# M.net
KiCad netlist of a schematic drawn in Altium Designer
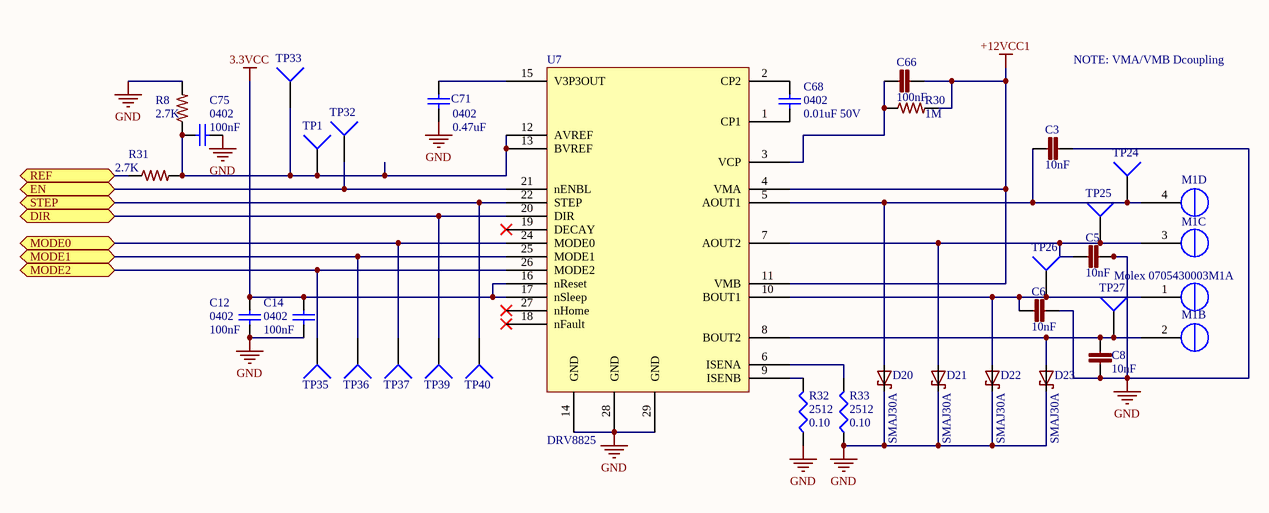
[diagram p0: M.SchDoc]

(export (version "E")
  (design (tool "Eeschema 10.0.6"))
  (components
    (comp (ref "C3")
      (value "10nF")
      (footprint "C0603")
      (description "CAP CER 0603 10nF 25V 10% X7R")
      (fields
        (field (name "MANUFACTURERPARTNUMBER") "C1608X7R1E103K080AA")
        (field (name "PUBLISHER") "UltiMachine")
      )
      (libsource (lib "3Delight") (part "C1608X7R1E103K080AA"))
    )
    (comp (ref "C5")
      (value "10nF")
      (footprint "C0603")
      (description "CAP CER 0603 10nF 25V 10% X7R")
      (fields
        (field (name "MANUFACTURERPARTNUMBER") "C1608X7R1E103K080AA")
        (field (name "PUBLISHER") "UltiMachine")
      )
      (libsource (lib "3Delight") (part "C1608X7R1E103K080AA"))
    )
    (comp (ref "C6")
      (value "10nF")
      (footprint "C0603")
      (description "CAP CER 0603 10nF 25V 10% X7R")
      (fields
        (field (name "MANUFACTURERPARTNUMBER") "C1608X7R1E103K080AA")
        (field (name "PUBLISHER") "UltiMachine")
      )
      (libsource (lib "3Delight") (part "C1608X7R1E103K080AA"))
    )
    (comp (ref "C8")
      (value "10nF")
      (footprint "C0603")
      (description "CAP CER 0603 10nF 25V 10% X7R")
      (fields
        (field (name "MANUFACTURERPARTNUMBER") "C1608X7R1E103K080AA")
        (field (name "PUBLISHER") "UltiMachine")
      )
      (libsource (lib "") (part "C1608X7R1E103K080AA_1"))
    )
    (comp (ref "C12")
      (value "100nF")
      (footprint "C0402")
      (description "Capacitor (Semiconductor SIM Model)")
      (fields
        (field (name "MFR PART #") "GRM155R71C104KA88D")
        (field (name "MFR") "Murata")
        (field (name "PACKAGEREFERENCE") "0402")
        (field (name "PUBLISHER") "Ultimachine")
      )
      (libsource (lib "Tigershark3D") (part "100nF C0402 - GRM155R71C104KA88D"))
    )
    (comp (ref "C14")
      (value "100nF")
      (footprint "C0402")
      (description "Capacitor (Semiconductor SIM Model)")
      (fields
        (field (name "MFR PART #") "GRM155R71C104KA88D")
        (field (name "MFR") "Murata")
        (field (name "PACKAGEREFERENCE") "0402")
        (field (name "PUBLISHER") "Ultimachine")
      )
      (libsource (lib "Tigershark3D") (part "100nF C0402 - GRM155R71C104KA88D"))
    )
    (comp (ref "C66")
      (value "100nF")
      (footprint "C0603")
      (description "CAP CER 0603 100nF 50V 10% X7R")
      (fields
        (field (name "MANUFACTURERPARTNUMBER") "C0603C104K5RACTU")
        (field (name "PUBLISHER") "UltiMachine")
      )
      (libsource (lib "3Delight") (part "C0603C104K5RACTU"))
    )
    (comp (ref "C68")
      (value "0.01uF 50V")
      (footprint "C0402")
      (description "CAP CER 10000PF 50V X7R 0402")
      (fields
        (field (name "MFR PART #") "GRM155R71H103JA88D")
        (field (name "MFR") "Murata")
        (field (name "PACKAGEREFERENCE") "0402")
        (field (name "PUBLISHER") "Ultimachine")
      )
      (libsource (lib "Tigershark3D") (part "GRM155R71H103JA88D"))
    )
    (comp (ref "C71")
      (value "0.47uF")
      (footprint "C0402")
      (description "0.47uF 6.3v C0402 - GRM155R60J474KE19D")
      (fields
        (field (name "MFR PART #") "GRM155R60J474KE19D")
        (field (name "MFR") "Murata")
        (field (name "PACKAGEREFERENCE") "0402")
        (field (name "PUBLISHER") "Ultimachine")
      )
      (libsource (lib "Tigershark3D") (part "GRM155R60J474KE19D"))
    )
    (comp (ref "C75")
      (value "100nF")
      (footprint "C0402")
      (description "Capacitor (Semiconductor SIM Model)")
      (fields
        (field (name "MFR PART #") "GRM155R71C104KA88D")
        (field (name "MFR") "Murata")
        (field (name "PACKAGEREFERENCE") "0402")
        (field (name "PUBLISHER") "Ultimachine")
      )
      (libsource (lib "Tigershark3D") (part "100nF C0402 - GRM155R71C104KA88D"))
    )
    (comp (ref "D20")
      (value "SMAJ30A")
      (footprint "SMA-SM")
      (description "DIODE TVS 30V SMA")
      (fields (field (name "PUBLISHER") "UltiMachine"))
      (libsource (lib "Tigershark3D") (part "SMAJ30A"))
    )
    (comp (ref "D21")
      (value "SMAJ30A")
      (footprint "SMA-SM")
      (description "DIODE TVS 30V SMA")
      (fields (field (name "PUBLISHER") "UltiMachine"))
      (libsource (lib "Tigershark3D") (part "SMAJ30A"))
    )
    (comp (ref "D22")
      (value "SMAJ30A")
      (footprint "SMA-SM")
      (description "DIODE TVS 30V SMA")
      (fields (field (name "PUBLISHER") "UltiMachine"))
      (libsource (lib "Tigershark3D") (part "SMAJ30A"))
    )
    (comp (ref "D23")
      (value "SMAJ30A")
      (footprint "SMA-SM")
      (description "DIODE TVS 30V SMA")
      (fields (field (name "PUBLISHER") "UltiMachine"))
      (libsource (lib "Tigershark3D") (part "SMAJ30A"))
    )
    (comp (ref "M1")
      (value "Molex 0705430003")
      (footprint "Molex 0705430003")
      (description "Molex 4 Pin Clip Connector")
      (libsource (lib "ZMBo Schematic Library") (part "Molex 0705430003 Alt"))
    )
    (comp (ref "R8")
      (value "2.7K")
      (footprint "R0402")
      (description "RES SMD 2.7K OHM 1% 1/10W 0402")
      (fields
        (field (name "MANUFACTURER") "Panasonic")
        (field (name "MANUFACTURERPARTNUMBER") "ERJ2GEJ105X")
        (field (name "PUBLISHER") "Adam")
      )
      (libsource (lib "Tigershark3D") (part "ERJ-2RKF2701X"))
    )
    (comp (ref "R30")
      (value "1M")
      (footprint "R0402")
      (description "RES 0402 1M 100mW 5%")
      (fields (field (name "MANUFACTURERPARTNUMBER") "ERJ2GEJ105X") (field (name "PUBLISHER") "UltiMachine"))
      (libsource (lib "Tigershark3D") (part "ERJ2GEJ105X"))
    )
    (comp (ref "R31")
      (value "2.7K")
      (footprint "R0402")
      (description "RES SMD 2.7K OHM 1% 1/10W 0402")
      (fields
        (field (name "MANUFACTURER") "Panasonic")
        (field (name "MANUFACTURERPARTNUMBER") "ERJ2GEJ105X")
        (field (name "PUBLISHER") "Adam")
      )
      (libsource (lib "Tigershark3D") (part "ERJ-2RKF2701X"))
    )
    (comp (ref "R32")
      (value "2512")
      (footprint "2512R-0.55")
      (description "RES SMD 0.1 OHM 1% 2W 2512")
      (fields (field (name "MFR") "Stackpole ELectronics Inc") (field (name "ALTIUM_VALUE") "0.10"))
      (libsource (lib "Tigershark3D") (part "CSRN2512FTR100"))
    )
    (comp (ref "R33")
      (value "2512")
      (footprint "2512R-0.55")
      (description "RES SMD 0.1 OHM 1% 2W 2512")
      (fields (field (name "MFR") "Stackpole ELectronics Inc") (field (name "ALTIUM_VALUE") "0.10"))
      (libsource (lib "Tigershark3D") (part "CSRN2512FTR100"))
    )
    (comp (ref "TP1")
      (value "TP4")
      (footprint "TP-2")
      (description "Socket")
      (fields (field (name "PUBLISHER") "Altium Limited"))
      (libsource (lib "ZMBo Schematic Library") (part "Socket"))
    )
    (comp (ref "TP24")
      (value "TP4")
      (footprint "TP-2")
      (description "Socket")
      (fields (field (name "PUBLISHER") "Altium Limited"))
      (libsource (lib "ZMBo Schematic Library") (part "Socket"))
    )
    (comp (ref "TP25")
      (value "TP4")
      (footprint "TP-2")
      (description "Socket")
      (fields (field (name "PUBLISHER") "Altium Limited"))
      (libsource (lib "ZMBo Schematic Library") (part "Socket"))
    )
    (comp (ref "TP26")
      (value "TP4")
      (footprint "TP-2")
      (description "Socket")
      (fields (field (name "PUBLISHER") "Altium Limited"))
      (libsource (lib "ZMBo Schematic Library") (part "Socket"))
    )
    (comp (ref "TP27")
      (value "TP4")
      (footprint "TP-2")
      (description "Socket")
      (fields (field (name "PUBLISHER") "Altium Limited"))
      (libsource (lib "ZMBo Schematic Library") (part "Socket"))
    )
    (comp (ref "TP32")
      (value "TP4")
      (footprint "TP-2")
      (description "Socket")
      (fields (field (name "PUBLISHER") "Altium Limited"))
      (libsource (lib "ZMBo Schematic Library") (part "Socket"))
    )
    (comp (ref "TP33")
      (value "TP4")
      (footprint "TP-2")
      (description "Socket")
      (fields (field (name "PUBLISHER") "Altium Limited"))
      (libsource (lib "ZMBo Schematic Library") (part "Socket"))
    )
    (comp (ref "TP35")
      (value "TP4")
      (footprint "TP-2")
      (description "Socket")
      (fields (field (name "PUBLISHER") "Altium Limited"))
      (libsource (lib "ZMBo Schematic Library") (part "Socket"))
    )
    (comp (ref "TP36")
      (value "TP4")
      (footprint "TP-2")
      (description "Socket")
      (fields (field (name "PUBLISHER") "Altium Limited"))
      (libsource (lib "ZMBo Schematic Library") (part "Socket"))
    )
    (comp (ref "TP37")
      (value "TP4")
      (footprint "TP-2")
      (description "Socket")
      (fields (field (name "PUBLISHER") "Altium Limited"))
      (libsource (lib "ZMBo Schematic Library") (part "Socket"))
    )
    (comp (ref "TP39")
      (value "TP4")
      (footprint "TP-2")
      (description "Socket")
      (fields (field (name "PUBLISHER") "Altium Limited"))
      (libsource (lib "ZMBo Schematic Library") (part "Socket"))
    )
    (comp (ref "TP40")
      (value "TP4")
      (footprint "TP-2")
      (description "Socket")
      (fields (field (name "PUBLISHER") "Altium Limited"))
      (libsource (lib "ZMBo Schematic Library") (part "Socket"))
    )
    (comp (ref "U7")
      (value "DRV8825")
      (footprint "DRV8825PWPR")
      (description "DRV8825 Ti Stepper Driver")
      (fields (field (name "PART NUMBER") "DRV8825PWPR") (field (name "VOLTAGE") "8.2-45VDC"))
      (libsource (lib "Tigershark3D") (part "DRV8825"))
    )
  )
  (nets
    (net (code "1") (name "+12VCC1") (class "Default")
      (node (ref "C66") (pin "2") (pinfunction "2_2") (pintype "passive"))
      (node (ref "R30") (pin "2") (pinfunction "2_2") (pintype "passive"))
      (node (ref "U7") (pin "11") (pinfunction "VMB_11") (pintype "passive"))
      (node (ref "U7") (pin "4") (pinfunction "VMA_4") (pintype "passive"))
    )
    (net (code "2") (name "/DIR") (class "Default")
      (node (ref "TP39") (pin "1") (pinfunction "1_1") (pintype "passive"))
      (node (ref "U7") (pin "20") (pinfunction "DIR_20") (pintype "passive"))
    )
    (net (code "3") (name "/EN") (class "Default")
      (node (ref "TP32") (pin "1") (pinfunction "1_1") (pintype "passive"))
      (node (ref "U7") (pin "21") (pinfunction "nENBL_21") (pintype "passive"))
    )
    (net (code "4") (name "/MODE0") (class "Default")
      (node (ref "TP37") (pin "1") (pinfunction "1_1") (pintype "passive"))
      (node (ref "U7") (pin "24") (pinfunction "MODE0_24") (pintype "passive"))
    )
    (net (code "5") (name "/MODE1") (class "Default")
      (node (ref "TP36") (pin "1") (pinfunction "1_1") (pintype "passive"))
      (node (ref "U7") (pin "25") (pinfunction "MODE1_25") (pintype "passive"))
    )
    (net (code "6") (name "/MODE2") (class "Default")
      (node (ref "TP35") (pin "1") (pinfunction "1_1") (pintype "passive"))
      (node (ref "U7") (pin "26") (pinfunction "MODE2_26") (pintype "passive"))
    )
    (net (code "7") (name "/REF") (class "Default")
      (node (ref "R31") (pin "1") (pinfunction "1_1") (pintype "passive"))
    )
    (net (code "8") (name "/STEP") (class "Default")
      (node (ref "TP40") (pin "1") (pinfunction "1_1") (pintype "passive"))
      (node (ref "U7") (pin "22") (pinfunction "STEP_22") (pintype "passive"))
    )
    (net (code "9") (name "3.3VCC") (class "Default")
      (node (ref "C12") (pin "2") (pinfunction "2_2") (pintype "passive"))
      (node (ref "C14") (pin "2") (pinfunction "2_2") (pintype "passive"))
      (node (ref "U7") (pin "16") (pinfunction "nReset_16") (pintype "passive"))
      (node (ref "U7") (pin "17") (pinfunction "nSleep_17") (pintype "passive"))
    )
    (net (code "10") (name "GND") (class "Default")
      (node (ref "C12") (pin "1") (pinfunction "1_1") (pintype "passive"))
      (node (ref "C14") (pin "1") (pinfunction "1_1") (pintype "passive"))
      (node (ref "C3") (pin "2") (pinfunction "2_2") (pintype "passive"))
      (node (ref "C5") (pin "2") (pinfunction "2_2") (pintype "passive"))
      (node (ref "C6") (pin "2") (pinfunction "2_2") (pintype "passive"))
      (node (ref "C71") (pin "1") (pinfunction "1_1") (pintype "passive"))
      (node (ref "C75") (pin "1") (pinfunction "1_1") (pintype "passive"))
      (node (ref "C8") (pin "1") (pinfunction "1_1") (pintype "passive"))
      (node (ref "D20") (pin "C") (pinfunction "C_C") (pintype "passive"))
      (node (ref "D21") (pin "C") (pinfunction "C_C") (pintype "passive"))
      (node (ref "D22") (pin "C") (pinfunction "C_C") (pintype "passive"))
      (node (ref "D23") (pin "C") (pinfunction "C_C") (pintype "passive"))
      (node (ref "R32") (pin "1") (pinfunction "1_1") (pintype "passive"))
      (node (ref "R33") (pin "1") (pinfunction "1_1") (pintype "passive"))
      (node (ref "R8") (pin "2") (pinfunction "2_2") (pintype "passive"))
      (node (ref "U7") (pin "14") (pinfunction "GND_14") (pintype "passive"))
      (node (ref "U7") (pin "28") (pinfunction "GND_28") (pintype "passive"))
      (node (ref "U7") (pin "29") (pinfunction "GND_29") (pintype "passive"))
    )
    (net (code "11") (name "Net-(M1A-OUT2B)") (class "Default")
      (node (ref "C6") (pin "1") (pinfunction "1_1") (pintype "passive"))
      (node (ref "D22") (pin "A") (pinfunction "A_A") (pintype "passive"))
      (node (ref "M1") (pin "1") (pinfunction "OUT2B_1") (pintype "passive"))
      (node (ref "TP26") (pin "1") (pinfunction "1_1") (pintype "passive"))
      (node (ref "U7") (pin "10") (pinfunction "BOUT1_10") (pintype "passive"))
    )
    (net (code "12") (name "Net-(M1B-OUT2A)") (class "Default")
      (node (ref "C8") (pin "2") (pinfunction "2_2") (pintype "passive"))
      (node (ref "D23") (pin "A") (pinfunction "A_A") (pintype "passive"))
      (node (ref "M1") (pin "2") (pinfunction "OUT2A_2") (pintype "passive"))
      (node (ref "TP27") (pin "1") (pinfunction "1_1") (pintype "passive"))
      (node (ref "U7") (pin "8") (pinfunction "BOUT2_8") (pintype "passive"))
    )
    (net (code "13") (name "Net-(M1C-OUT1A)") (class "Default")
      (node (ref "C5") (pin "1") (pinfunction "1_1") (pintype "passive"))
      (node (ref "D21") (pin "A") (pinfunction "A_A") (pintype "passive"))
      (node (ref "M1") (pin "3") (pinfunction "OUT1A_3") (pintype "passive"))
      (node (ref "TP25") (pin "1") (pinfunction "1_1") (pintype "passive"))
      (node (ref "U7") (pin "7") (pinfunction "AOUT2_7") (pintype "passive"))
    )
    (net (code "14") (name "Net-(M1D-OUT1B)") (class "Default")
      (node (ref "C3") (pin "1") (pinfunction "1_1") (pintype "passive"))
      (node (ref "D20") (pin "A") (pinfunction "A_A") (pintype "passive"))
      (node (ref "M1") (pin "4") (pinfunction "OUT1B_4") (pintype "passive"))
      (node (ref "TP24") (pin "1") (pinfunction "1_1") (pintype "passive"))
      (node (ref "U7") (pin "5") (pinfunction "AOUT1_5") (pintype "passive"))
    )
    (net (code "15") (name "Net-(U7-AVREF)") (class "Default")
      (node (ref "C75") (pin "2") (pinfunction "2_2") (pintype "passive"))
      (node (ref "R31") (pin "2") (pinfunction "2_2") (pintype "passive"))
      (node (ref "R8") (pin "1") (pinfunction "1_1") (pintype "passive"))
      (node (ref "TP1") (pin "1") (pinfunction "1_1") (pintype "passive"))
      (node (ref "TP33") (pin "1") (pinfunction "1_1") (pintype "passive"))
      (node (ref "U7") (pin "12") (pinfunction "AVREF_12") (pintype "passive"))
      (node (ref "U7") (pin "13") (pinfunction "BVREF_13") (pintype "passive"))
    )
    (net (code "16") (name "Net-(U7-CP1)") (class "Default")
      (node (ref "C68") (pin "1") (pinfunction "1_1") (pintype "passive"))
      (node (ref "U7") (pin "1") (pinfunction "CP1_1") (pintype "passive"))
    )
    (net (code "17") (name "Net-(U7-CP2)") (class "Default")
      (node (ref "C68") (pin "2") (pinfunction "2_2") (pintype "passive"))
      (node (ref "U7") (pin "2") (pinfunction "CP2_2") (pintype "passive"))
    )
    (net (code "18") (name "Net-(U7-ISENA)") (class "Default")
      (node (ref "R33") (pin "2") (pinfunction "2_2") (pintype "passive"))
      (node (ref "U7") (pin "6") (pinfunction "ISENA_6") (pintype "passive"))
    )
    (net (code "19") (name "Net-(U7-ISENB)") (class "Default")
      (node (ref "R32") (pin "2") (pinfunction "2_2") (pintype "passive"))
      (node (ref "U7") (pin "9") (pinfunction "ISENB_9") (pintype "passive"))
    )
    (net (code "20") (name "Net-(U7-V3P3OUT)") (class "Default")
      (node (ref "C71") (pin "2") (pinfunction "2_2") (pintype "passive"))
      (node (ref "U7") (pin "15") (pinfunction "V3P3OUT_15") (pintype "passive"))
    )
    (net (code "21") (name "Net-(U7-VCP)") (class "Default")
      (node (ref "C66") (pin "1") (pinfunction "1_1") (pintype "passive"))
      (node (ref "R30") (pin "1") (pinfunction "1_1") (pintype "passive"))
      (node (ref "U7") (pin "3") (pinfunction "VCP_3") (pintype "passive"))
    )
    (net (code "22") (name "unconnected-(U7-DECAY-Pad19)") (class "Default")
      (node (ref "U7") (pin "19") (pinfunction "DECAY_19") (pintype "passive+no_connect"))
    )
    (net (code "23") (name "unconnected-(U7-NC-Pad23)") (class "Default")
      (node (ref "U7") (pin "23") (pinfunction "NC_23") (pintype "passive"))
    )
    (net (code "24") (name "unconnected-(U7-nFault-Pad18)") (class "Default")
      (node (ref "U7") (pin "18") (pinfunction "nFault_18") (pintype "passive+no_connect"))
    )
    (net (code "25") (name "unconnected-(U7-nHome-Pad27)") (class "Default")
      (node (ref "U7") (pin "27") (pinfunction "nHome_27") (pintype "passive+no_connect"))
    )
  )
)
